# FPGA_POWER_AND_CONFIGURATION.net
KiCad netlist of a schematic drawn in Altium Designer
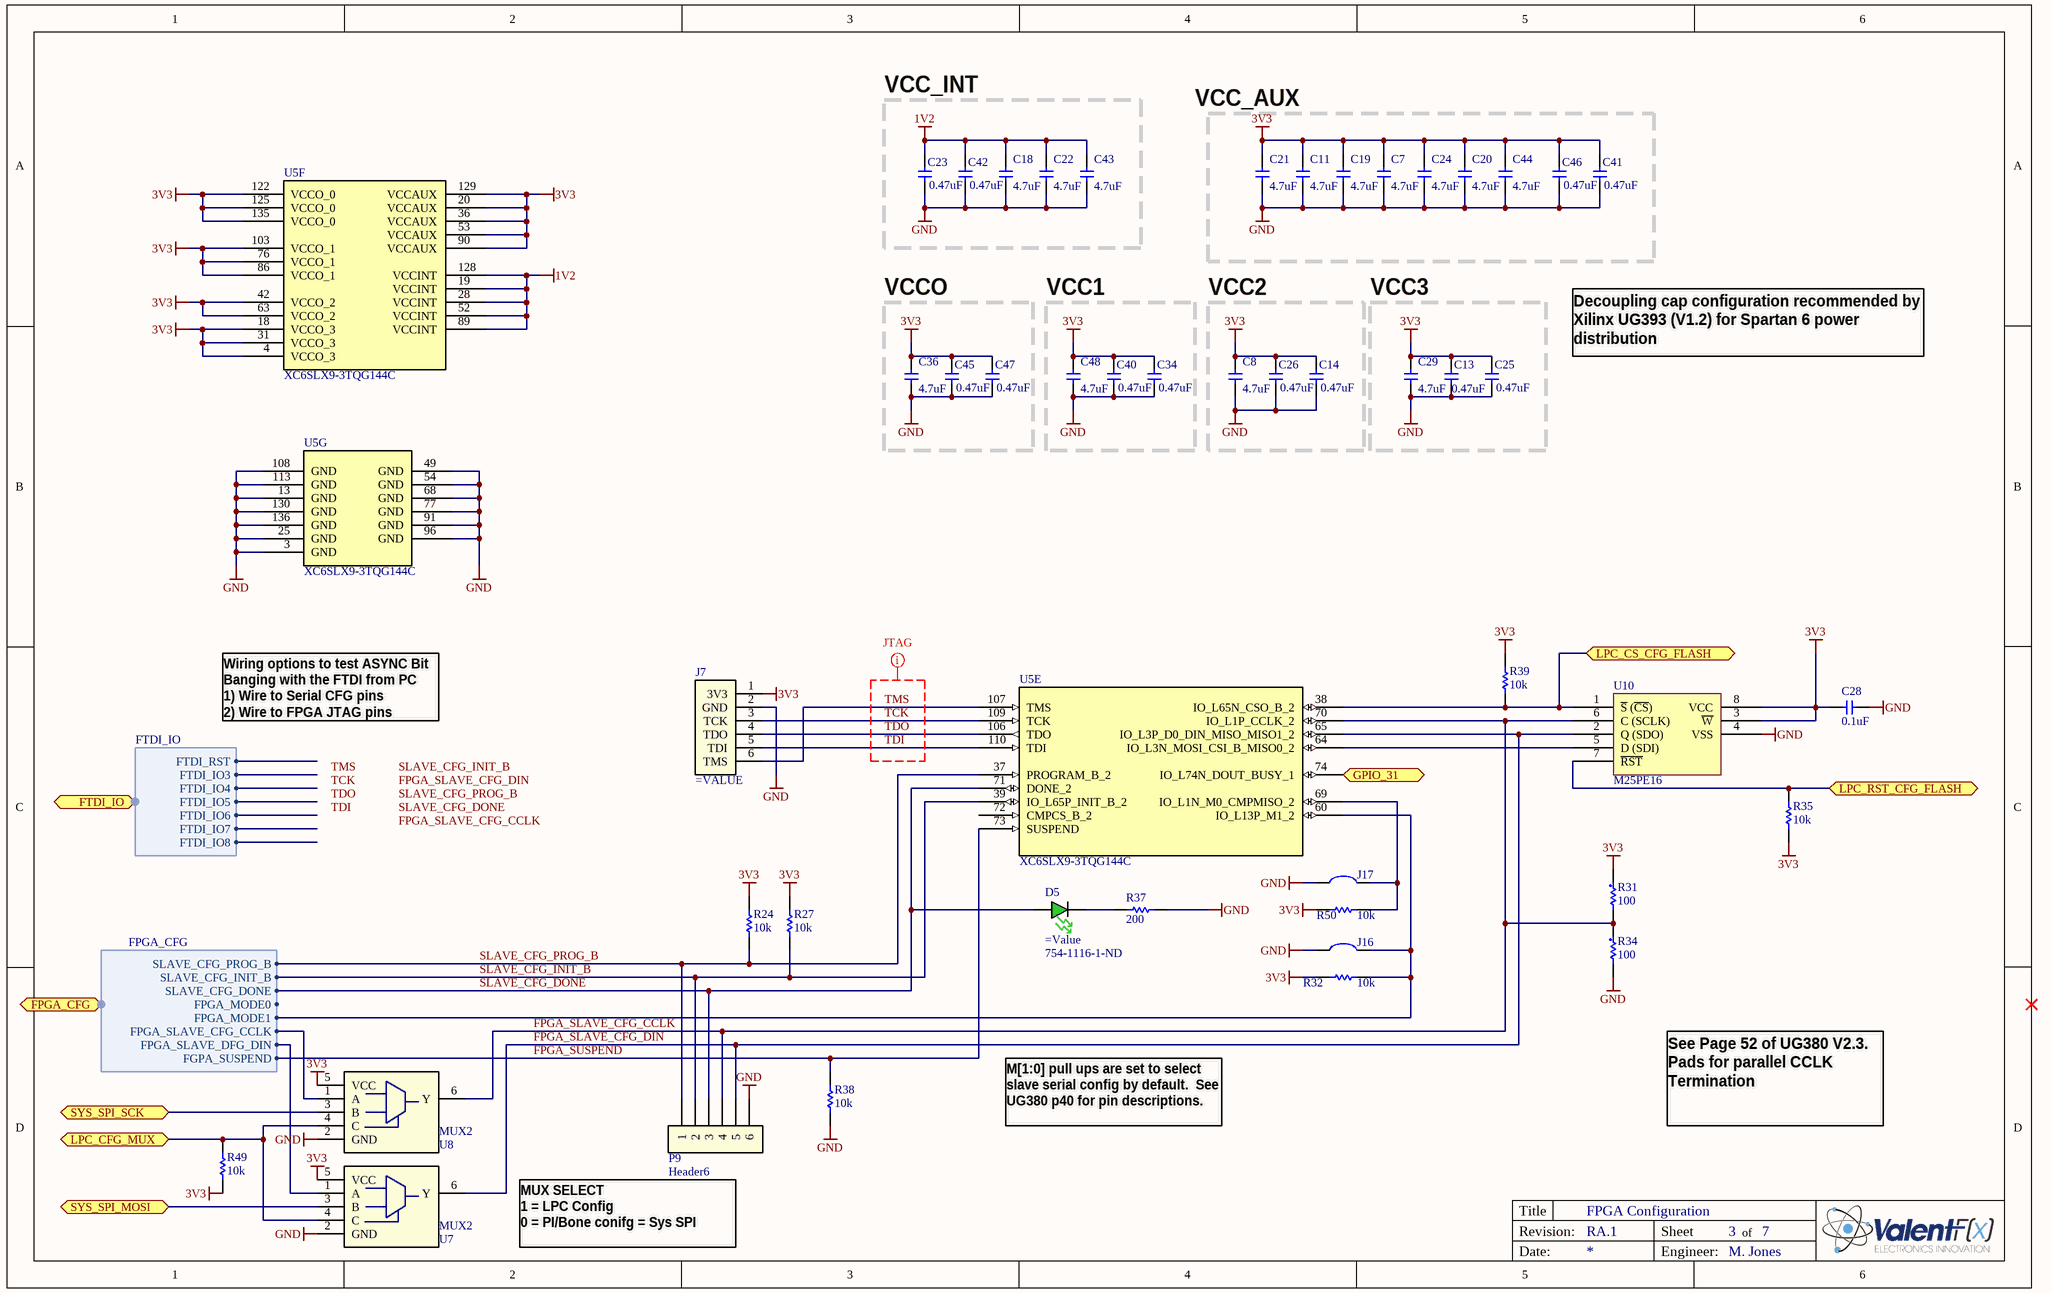
[diagram p0: FPGA_POWER_AND_CONFIGURATION.SchDoc]

(export (version "E")
  (design (tool "Eeschema 10.0.6"))
  (components
    (comp (ref "C7")
      (value "4.7uF")
      (footprint "C0603")
      (description "CAP CER 4.7UF 6.3V X5R 0603")
      (fields
        (field (name "MANUFACTURER") "Murata Electronics North America")
        (field (name "MANUFACTURER PART NUMBER") "GRM188R60J475KE19D")
      )
      (libsource (lib "eCapacitors") (part "GRM188R60J475KE19D"))
    )
    (comp (ref "C8")
      (value "4.7uF")
      (footprint "C0603")
      (description "CAP CER 4.7UF 6.3V X5R 0603")
      (fields
        (field (name "MANUFACTURER") "Murata Electronics North America")
        (field (name "MANUFACTURER PART NUMBER") "GRM188R60J475KE19D")
      )
      (libsource (lib "eCapacitors") (part "GRM188R60J475KE19D"))
    )
    (comp (ref "C11")
      (value "4.7uF")
      (footprint "C0603")
      (description "CAP CER 4.7UF 6.3V X5R 0603")
      (fields
        (field (name "MANUFACTURER") "Murata Electronics North America")
        (field (name "MANUFACTURER PART NUMBER") "GRM188R60J475KE19D")
      )
      (libsource (lib "eCapacitors") (part "GRM188R60J475KE19D"))
    )
    (comp (ref "C13")
      (value "0.47uF")
      (footprint "C0603")
      (description "CAP CER .47UF 25V X7R 0603")
      (fields
        (field (name "MANUFACTURER") "Murata Electronics North America")
        (field (name "MANUFACTURER PART NUMBER") "GCM188R71E474KA64D")
      )
      (libsource (lib "eCapacitors") (part "GCM188R71E474KA64D"))
    )
    (comp (ref "C14")
      (value "0.47uF")
      (footprint "C0603")
      (description "CAP CER .47UF 25V X7R 0603")
      (fields
        (field (name "MANUFACTURER") "Murata Electronics North America")
        (field (name "MANUFACTURER PART NUMBER") "GCM188R71E474KA64D")
      )
      (libsource (lib "eCapacitors") (part "GCM188R71E474KA64D"))
    )
    (comp (ref "C18")
      (value "4.7uF")
      (footprint "C0603")
      (description "CAP CER 4.7UF 6.3V X5R 0603")
      (fields
        (field (name "MANUFACTURER") "Murata Electronics North America")
        (field (name "MANUFACTURER PART NUMBER") "GRM188R60J475KE19D")
      )
      (libsource (lib "eCapacitors") (part "GRM188R60J475KE19D"))
    )
    (comp (ref "C19")
      (value "4.7uF")
      (footprint "C0603")
      (description "CAP CER 4.7UF 6.3V X5R 0603")
      (fields
        (field (name "MANUFACTURER") "Murata Electronics North America")
        (field (name "MANUFACTURER PART NUMBER") "GRM188R60J475KE19D")
      )
      (libsource (lib "eCapacitors") (part "GRM188R60J475KE19D"))
    )
    (comp (ref "C20")
      (value "4.7uF")
      (footprint "C0603")
      (description "CAP CER 4.7UF 6.3V X5R 0603")
      (fields
        (field (name "MANUFACTURER") "Murata Electronics North America")
        (field (name "MANUFACTURER PART NUMBER") "GRM188R60J475KE19D")
      )
      (libsource (lib "eCapacitors") (part "GRM188R60J475KE19D"))
    )
    (comp (ref "C21")
      (value "4.7uF")
      (footprint "C0603")
      (description "CAP CER 4.7UF 6.3V X5R 0603")
      (fields
        (field (name "MANUFACTURER") "Murata Electronics North America")
        (field (name "MANUFACTURER PART NUMBER") "GRM188R60J475KE19D")
      )
      (libsource (lib "eCapacitors") (part "GRM188R60J475KE19D"))
    )
    (comp (ref "C22")
      (value "4.7uF")
      (footprint "C0603")
      (description "CAP CER 4.7UF 6.3V X5R 0603")
      (fields
        (field (name "MANUFACTURER") "Murata Electronics North America")
        (field (name "MANUFACTURER PART NUMBER") "GRM188R60J475KE19D")
      )
      (libsource (lib "eCapacitors") (part "GRM188R60J475KE19D"))
    )
    (comp (ref "C23")
      (value "0.47uF")
      (footprint "C0603")
      (description "CAP CER .47UF 25V X7R 0603")
      (fields
        (field (name "MANUFACTURER") "Murata Electronics North America")
        (field (name "MANUFACTURER PART NUMBER") "GCM188R71E474KA64D")
      )
      (libsource (lib "eCapacitors") (part "GCM188R71E474KA64D"))
    )
    (comp (ref "C24")
      (value "4.7uF")
      (footprint "C0603")
      (description "CAP CER 4.7UF 6.3V X5R 0603")
      (fields
        (field (name "MANUFACTURER") "Murata Electronics North America")
        (field (name "MANUFACTURER PART NUMBER") "GRM188R60J475KE19D")
      )
      (libsource (lib "eCapacitors") (part "GRM188R60J475KE19D"))
    )
    (comp (ref "C25")
      (value "0.47uF")
      (footprint "C0603")
      (description "CAP CER .47UF 25V X7R 0603")
      (fields
        (field (name "MANUFACTURER") "Murata Electronics North America")
        (field (name "MANUFACTURER PART NUMBER") "GCM188R71E474KA64D")
      )
      (libsource (lib "eCapacitors") (part "GCM188R71E474KA64D"))
    )
    (comp (ref "C26")
      (value "0.47uF")
      (footprint "C0603")
      (description "CAP CER .47UF 25V X7R 0603")
      (fields
        (field (name "MANUFACTURER") "Murata Electronics North America")
        (field (name "MANUFACTURER PART NUMBER") "GCM188R71E474KA64D")
      )
      (libsource (lib "eCapacitors") (part "GCM188R71E474KA64D"))
    )
    (comp (ref "C28")
      (value "0.1uF")
      (footprint "C0603")
      (description "CAP CER .1UF 50V 10% X7R 0603")
      (fields
        (field (name "MANUFACTURER") "Murata Electronics North America")
        (field (name "MANUFACTURER PART NUMBER") "GRM188R71H104KA93D")
      )
      (libsource (lib "eCapacitors") (part "GRM188R71H104KA93D"))
    )
    (comp (ref "C29")
      (value "4.7uF")
      (footprint "C0603")
      (description "CAP CER 4.7UF 6.3V X5R 0603")
      (fields
        (field (name "MANUFACTURER") "Murata Electronics North America")
        (field (name "MANUFACTURER PART NUMBER") "GRM188R60J475KE19D")
      )
      (libsource (lib "eCapacitors") (part "GRM188R60J475KE19D"))
    )
    (comp (ref "C34")
      (value "0.47uF")
      (footprint "C0603")
      (description "CAP CER .47UF 25V X7R 0603")
      (fields
        (field (name "MANUFACTURER") "Murata Electronics North America")
        (field (name "MANUFACTURER PART NUMBER") "GCM188R71E474KA64D")
      )
      (libsource (lib "eCapacitors") (part "GCM188R71E474KA64D"))
    )
    (comp (ref "C36")
      (value "4.7uF")
      (footprint "C0603")
      (description "CAP CER 4.7UF 6.3V X5R 0603")
      (fields
        (field (name "MANUFACTURER") "Murata Electronics North America")
        (field (name "MANUFACTURER PART NUMBER") "GRM188R60J475KE19D")
      )
      (libsource (lib "eCapacitors") (part "GRM188R60J475KE19D"))
    )
    (comp (ref "C40")
      (value "0.47uF")
      (footprint "C0603")
      (description "CAP CER .47UF 25V X7R 0603")
      (fields
        (field (name "MANUFACTURER") "Murata Electronics North America")
        (field (name "MANUFACTURER PART NUMBER") "GCM188R71E474KA64D")
      )
      (libsource (lib "eCapacitors") (part "GCM188R71E474KA64D"))
    )
    (comp (ref "C41")
      (value "0.47uF")
      (footprint "C0603")
      (description "CAP CER .47UF 25V X7R 0603")
      (fields
        (field (name "MANUFACTURER") "Murata Electronics North America")
        (field (name "MANUFACTURER PART NUMBER") "GCM188R71E474KA64D")
      )
      (libsource (lib "eCapacitors") (part "GCM188R71E474KA64D"))
    )
    (comp (ref "C42")
      (value "0.47uF")
      (footprint "C0603")
      (description "CAP CER .47UF 25V X7R 0603")
      (fields
        (field (name "MANUFACTURER") "Murata Electronics North America")
        (field (name "MANUFACTURER PART NUMBER") "GCM188R71E474KA64D")
      )
      (libsource (lib "eCapacitors") (part "GCM188R71E474KA64D"))
    )
    (comp (ref "C43")
      (value "4.7uF")
      (footprint "C0603")
      (description "CAP CER 4.7UF 6.3V X5R 0603")
      (fields
        (field (name "MANUFACTURER") "Murata Electronics North America")
        (field (name "MANUFACTURER PART NUMBER") "GRM188R60J475KE19D")
      )
      (libsource (lib "eCapacitors") (part "GRM188R60J475KE19D"))
    )
    (comp (ref "C44")
      (value "4.7uF")
      (footprint "C0603")
      (description "CAP CER 4.7UF 6.3V X5R 0603")
      (fields
        (field (name "MANUFACTURER") "Murata Electronics North America")
        (field (name "MANUFACTURER PART NUMBER") "GRM188R60J475KE19D")
      )
      (libsource (lib "eCapacitors") (part "GRM188R60J475KE19D"))
    )
    (comp (ref "C45")
      (value "0.47uF")
      (footprint "C0603")
      (description "CAP CER .47UF 25V X7R 0603")
      (fields
        (field (name "MANUFACTURER") "Murata Electronics North America")
        (field (name "MANUFACTURER PART NUMBER") "GCM188R71E474KA64D")
      )
      (libsource (lib "eCapacitors") (part "GCM188R71E474KA64D"))
    )
    (comp (ref "C46")
      (value "0.47uF")
      (footprint "C0603")
      (description "CAP CER .47UF 25V X7R 0603")
      (fields
        (field (name "MANUFACTURER") "Murata Electronics North America")
        (field (name "MANUFACTURER PART NUMBER") "GCM188R71E474KA64D")
      )
      (libsource (lib "eCapacitors") (part "GCM188R71E474KA64D"))
    )
    (comp (ref "C47")
      (value "0.47uF")
      (footprint "C0603")
      (description "CAP CER .47UF 25V X7R 0603")
      (fields
        (field (name "MANUFACTURER") "Murata Electronics North America")
        (field (name "MANUFACTURER PART NUMBER") "GCM188R71E474KA64D")
      )
      (libsource (lib "eCapacitors") (part "GCM188R71E474KA64D"))
    )
    (comp (ref "C48")
      (value "4.7uF")
      (footprint "C0603")
      (description "CAP CER 4.7UF 6.3V X5R 0603")
      (fields
        (field (name "MANUFACTURER") "Murata Electronics North America")
        (field (name "MANUFACTURER PART NUMBER") "GRM188R60J475KE19D")
      )
      (libsource (lib "eCapacitors") (part "GRM188R60J475KE19D"))
    )
    (comp (ref "D5")
      (value "~")
      (footprint "LED_0603 - GREEN")
      (description "LED 1.6X0.8MM 570NM GRN CLR SMD")
      (fields
        (field (name "SUPPLIER PART NUMBER 1") "754-1116-1-ND")
        (field (name "MANUFACTURER") "Kingbright Corp")
        (field (name "MANUFACTURER PART NUMBER") "APT1608CGCK")
      )
      (libsource (lib "mDiode") (part "APT1608CGCK"))
    )
    (comp (ref "J7")
      (value "~")
      (footprint "JTAG - Digilent HS1")
      (description "DIGILENT - 410-205 - PROGRAMMING CABLE, JTAG HS1, USB2")
      (fields
        (field (name "MANUFACTURER") "Samtec")
        (field (name "MANUFACTURER PART NUMBER") "TSW-106-08-G-S-RA")
      )
      (libsource (lib "mConnector") (part "JTAG - Digilent HS1"))
    )
    (comp (ref "J16")
      (value "Solder Jumper")
      (footprint "SOLDER_JUMPER")
      (description "Solder/Configuration Jumper")
      (fields (field (name "MANUFACTURER") "n/a"))
      (libsource (lib "eConnector") (part "Solder Jumper"))
    )
    (comp (ref "J17")
      (value "Solder Jumper")
      (footprint "SOLDER_JUMPER")
      (description "Solder/Configuration Jumper")
      (fields (field (name "MANUFACTURER") "n/a"))
      (libsource (lib "eConnector") (part "Solder Jumper"))
    )
    (comp (ref "P9")
      (value "Header6")
      (footprint "HEADER_6_30_100 SMT SIP")
      (description "Header 6 pin")
      (libsource (lib "mConnector") (part "Header6"))
    )
    (comp (ref "R24")
      (value "10k")
      (footprint "R0603")
      (description "RES 10.0K OHM 1/10W 1% 0603 SMD")
      (fields
        (field (name "MANUFACTURER") "Panasonic - ECG")
        (field (name "MANUFACTURER PART NUMBER") "ERJ-3EKF1002V")
      )
      (libsource (lib "eResistors") (part "ERJ-3EKF1002V"))
    )
    (comp (ref "R27")
      (value "10k")
      (footprint "R0603")
      (description "RES 10.0K OHM 1/10W 1% 0603 SMD")
      (fields
        (field (name "MANUFACTURER") "Panasonic - ECG")
        (field (name "MANUFACTURER PART NUMBER") "ERJ-3EKF1002V")
      )
      (libsource (lib "eResistors") (part "ERJ-3EKF1002V"))
    )
    (comp (ref "R31")
      (value "100")
      (footprint "mRCL:R0603")
      (description "100 ohms 1% Thick Film Resistors - SMD 1/10watt")
      (fields
        (field (name "MANUFACTURER") "Vishay/Dale")
        (field (name "MANUFACTURER PART NUMBER") "CRCW0603100RFKEA")
      )
      (libsource (lib "mResistors") (part "R0603 - CRCW0603100RFKEA"))
    )
    (comp (ref "R32")
      (value "10k")
      (footprint "R0603")
      (description "RES 10.0K OHM 1/10W 1% 0603 SMD")
      (fields
        (field (name "MANUFACTURER") "Panasonic - ECG")
        (field (name "MANUFACTURER PART NUMBER") "ERJ-3EKF1002V")
      )
      (libsource (lib "eResistors") (part "ERJ-3EKF1002V"))
    )
    (comp (ref "R34")
      (value "100")
      (footprint "mRCL:R0603")
      (description "100 ohms 1% Thick Film Resistors - SMD 1/10watt")
      (fields
        (field (name "MANUFACTURER") "Vishay/Dale")
        (field (name "MANUFACTURER PART NUMBER") "CRCW0603100RFKEA")
      )
      (libsource (lib "mResistors") (part "R0603 - CRCW0603100RFKEA"))
    )
    (comp (ref "R35")
      (value "10k")
      (footprint "R0603")
      (description "RES 10.0K OHM 1/10W 1% 0603 SMD")
      (fields
        (field (name "MANUFACTURER") "Panasonic - ECG")
        (field (name "MANUFACTURER PART NUMBER") "ERJ-3EKF1002V")
      )
      (libsource (lib "eResistors") (part "ERJ-3EKF1002V"))
    )
    (comp (ref "R37")
      (value "200")
      (footprint "R0603")
      (description "RES 200 OHM 1/10W 1% 0603 SMD")
      (fields
        (field (name "MANUFACTURER") "Panasonic - ECG")
        (field (name "MANUFACTURER PART NUMBER") "ERJ-3EKF2000V")
      )
      (libsource (lib "eResistors") (part "ERJ-3EKF2000V"))
    )
    (comp (ref "R38")
      (value "10k")
      (footprint "R0603")
      (description "RES 10.0K OHM 1/10W 1% 0603 SMD")
      (fields
        (field (name "MANUFACTURER") "Panasonic - ECG")
        (field (name "MANUFACTURER PART NUMBER") "ERJ-3EKF1002V")
      )
      (libsource (lib "eResistors") (part "ERJ-3EKF1002V"))
    )
    (comp (ref "R39")
      (value "10k")
      (footprint "R0603")
      (description "RES 10.0K OHM 1/10W 1% 0603 SMD")
      (fields
        (field (name "MANUFACTURER") "Panasonic - ECG")
        (field (name "MANUFACTURER PART NUMBER") "ERJ-3EKF1002V")
      )
      (libsource (lib "eResistors") (part "ERJ-3EKF1002V"))
    )
    (comp (ref "R49")
      (value "10k")
      (footprint "R0603")
      (description "RES 10.0K OHM 1/10W 1% 0603 SMD")
      (fields
        (field (name "MANUFACTURER") "Panasonic - ECG")
        (field (name "MANUFACTURER PART NUMBER") "ERJ-3EKF1002V")
      )
      (libsource (lib "eResistors") (part "ERJ-3EKF1002V"))
    )
    (comp (ref "R50")
      (value "10k")
      (footprint "R0603")
      (description "RES 10.0K OHM 1/10W 1% 0603 SMD")
      (fields
        (field (name "MANUFACTURER") "Panasonic - ECG")
        (field (name "MANUFACTURER PART NUMBER") "ERJ-3EKF1002V")
      )
      (libsource (lib "eResistors") (part "ERJ-3EKF1002V"))
    )
    (comp (ref "U5")
      (value "XC6SLX9-3TQG144C")
      (footprint "TQ144_L")
      (description "IC FPAG SPARTAN 6 9K 144TQFP")
      (fields (field (name "MANUFACTURER") "Xilinx Inc"))
      (libsource (lib "eIC") (part "XC6SLX9-3TQG144C"))
    )
    (comp (ref "U7")
      (value "MUX2")
      (footprint "SC70-6")
      (description "IC BUFF/MUX SCHMITT-TRIG SC70-6")
      (fields
        (field (name "MANUFACTURER") "Texas Instruments")
        (field (name "MANUFACTURER PART NUMBER") "SN74AUP1T157DCKR")
      )
      (libsource (lib "mIC") (part "MUX - SN74AUP1T157DCKR"))
    )
    (comp (ref "U8")
      (value "MUX2")
      (footprint "SC70-6")
      (description "IC BUFF/MUX SCHMITT-TRIG SC70-6")
      (fields
        (field (name "MANUFACTURER") "Texas Instruments")
        (field (name "MANUFACTURER PART NUMBER") "SN74AUP1T157DCKR")
      )
      (libsource (lib "mIC") (part "MUX - SN74AUP1T157DCKR"))
    )
    (comp (ref "U10")
      (value "M25PE16")
      (footprint "SOIC127P830X200-8L")
      (description "IC FLASH 16MBIT 75MHZ 8SOIC")
      (fields
        (field (name "MANUFACTURER") "Numonyx/ST Micro")
        (field (name "MANUFACTURER PART NUMBER") "M25PE16-VMW6TG")
      )
      (libsource (lib "ICs") (part "M25PE16-VMW6TG"))
    )
  )
  (nets
    (net (code "3") (name "/FPGA_MODE1") (class "Default")
      (node (ref "J16") (pin "1") (pinfunction "1_1") (pintype "passive"))
      (node (ref "R32") (pin "2") (pinfunction "2_2") (pintype "passive"))
      (node (ref "U5") (pin "60") (pinfunction "IO_L13P_M1_2_60") (pintype "bidirectional"))
    )
    (net (code "4") (name "/FPGA_SLAVE_CFG_CCLK") (class "Default")
      (node (ref "P9") (pin "4") (pinfunction "4_4") (pintype "passive"))
      (node (ref "R31") (pin "2") (pinfunction "2_2") (pintype "passive"))
      (node (ref "R34") (pin "1") (pinfunction "1_1") (pintype "passive"))
      (node (ref "U10") (pin "6") (pinfunction "C_(SCLK)_6") (pintype "passive"))
      (node (ref "U5") (pin "70") (pinfunction "IO_L1P_CCLK_2_70") (pintype "bidirectional"))
      (node (ref "U8") (pin "6") (pinfunction "Y_6") (pintype "passive"))
    )
    (net (code "5") (name "/FPGA_SLAVE_CFG_DIN") (class "Default")
      (node (ref "P9") (pin "5") (pinfunction "5_5") (pintype "passive"))
      (node (ref "U10") (pin "2") (pinfunction "Q_(SDO)_2") (pintype "passive"))
      (node (ref "U5") (pin "65") (pinfunction "IO_L3P_D0_DIN_MISO_MISO1_2_65") (pintype "bidirectional"))
      (node (ref "U7") (pin "6") (pinfunction "Y_6") (pintype "passive"))
    )
    (net (code "6") (name "/FPGA_SLAVE_DFG_DIN") (class "Default")
      (node (ref "U7") (pin "1") (pinfunction "A_1") (pintype "passive"))
    )
    (net (code "7") (name "/FPGA_SUSPEND") (class "Default")
      (node (ref "R38") (pin "2") (pinfunction "2_2") (pintype "passive"))
      (node (ref "U5") (pin "73") (pinfunction "SUSPEND_73") (pintype "input"))
    )
    (net (code "15") (name "/GPIO_31") (class "Default")
      (node (ref "U5") (pin "74") (pinfunction "IO_L74N_DOUT_BUSY_1_74") (pintype "bidirectional"))
    )
    (net (code "16") (name "/LPC_CFG_MUX") (class "Default")
      (node (ref "R49") (pin "2") (pinfunction "2_2") (pintype "passive"))
      (node (ref "U7") (pin "4") (pinfunction "C_4") (pintype "passive"))
      (node (ref "U8") (pin "4") (pinfunction "C_4") (pintype "passive"))
    )
    (net (code "17") (name "/LPC_CS_CFG_FLASH") (class "Default")
      (node (ref "R39") (pin "1") (pinfunction "1_1") (pintype "passive"))
      (node (ref "U10") (pin "1") (pinfunction "~{S}_(~{CS})_1") (pintype "passive"))
      (node (ref "U5") (pin "38") (pinfunction "IO_L65N_CSO_B_2_38") (pintype "bidirectional"))
    )
    (net (code "18") (name "/LPC_RST_CFG_FLASH") (class "Default")
      (node (ref "R35") (pin "1") (pinfunction "1_1") (pintype "passive"))
      (node (ref "U10") (pin "7") (pinfunction "~{RST}_7") (pintype "passive"))
    )
    (net (code "19") (name "/SLAVE_CFG_DONE") (class "Default")
      (node (ref "D5") (pin "A") (pinfunction "A_A") (pintype "passive"))
      (node (ref "P9") (pin "3") (pinfunction "3_3") (pintype "passive"))
      (node (ref "U5") (pin "71") (pinfunction "DONE_2_71") (pintype "bidirectional"))
    )
    (net (code "20") (name "/SLAVE_CFG_INIT_B") (class "Default")
      (node (ref "P9") (pin "2") (pinfunction "2_2") (pintype "passive"))
      (node (ref "R27") (pin "1") (pinfunction "1_1") (pintype "passive"))
      (node (ref "U5") (pin "39") (pinfunction "IO_L65P_INIT_B_2_39") (pintype "bidirectional"))
    )
    (net (code "21") (name "/SLAVE_CFG_PROG_B") (class "Default")
      (node (ref "P9") (pin "1") (pinfunction "1_1") (pintype "passive"))
      (node (ref "R24") (pin "1") (pinfunction "1_1") (pintype "passive"))
      (node (ref "U5") (pin "37") (pinfunction "PROGRAM_B_2_37") (pintype "input"))
    )
    (net (code "22") (name "/SYS_SPI_MOSI") (class "Default")
      (node (ref "U7") (pin "3") (pinfunction "B_3") (pintype "passive"))
    )
    (net (code "23") (name "/SYS_SPI_SCK") (class "Default")
      (node (ref "U8") (pin "3") (pinfunction "B_3") (pintype "passive"))
    )
    (net (code "24") (name "/TCK") (class "Default")
      (node (ref "J7") (pin "3") (pinfunction "TCK_3") (pintype "passive"))
      (node (ref "U5") (pin "109") (pinfunction "TCK_109") (pintype "input"))
    )
    (net (code "25") (name "/TDI") (class "Default")
      (node (ref "J7") (pin "5") (pinfunction "TDI_5") (pintype "passive"))
      (node (ref "U5") (pin "110") (pinfunction "TDI_110") (pintype "input"))
    )
    (net (code "26") (name "/TDO") (class "Default")
      (node (ref "J7") (pin "4") (pinfunction "TDO_4") (pintype "passive"))
      (node (ref "U5") (pin "106") (pinfunction "TDO_106") (pintype "output"))
    )
    (net (code "27") (name "/TMS") (class "Default")
      (node (ref "J7") (pin "6") (pinfunction "TMS_6") (pintype "passive"))
      (node (ref "U5") (pin "107") (pinfunction "TMS_107") (pintype "input"))
    )
    (net (code "30") (name "1V2") (class "Default")
      (node (ref "C18") (pin "2") (pinfunction "2_2") (pintype "passive"))
      (node (ref "C22") (pin "2") (pinfunction "2_2") (pintype "passive"))
      (node (ref "C23") (pin "2") (pinfunction "2_2") (pintype "passive"))
      (node (ref "C42") (pin "2") (pinfunction "2_2") (pintype "passive"))
      (node (ref "C43") (pin "2") (pinfunction "2_2") (pintype "passive"))
      (node (ref "U5") (pin "128") (pinfunction "VCCINT_128") (pintype "power_in"))
      (node (ref "U5") (pin "19") (pinfunction "VCCINT_19") (pintype "power_in"))
      (node (ref "U5") (pin "28") (pinfunction "VCCINT_28") (pintype "power_in"))
      (node (ref "U5") (pin "52") (pinfunction "VCCINT_52") (pintype "power_in"))
      (node (ref "U5") (pin "89") (pinfunction "VCCINT_89") (pintype "power_in"))
    )
    (net (code "31") (name "3V3") (class "Default")
      (node (ref "C11") (pin "2") (pinfunction "2_2") (pintype "passive"))
      (node (ref "C13") (pin "2") (pinfunction "2_2") (pintype "passive"))
      (node (ref "C14") (pin "2") (pinfunction "2_2") (pintype "passive"))
      (node (ref "C19") (pin "2") (pinfunction "2_2") (pintype "passive"))
      (node (ref "C20") (pin "2") (pinfunction "2_2") (pintype "passive"))
      (node (ref "C21") (pin "2") (pinfunction "2_2") (pintype "passive"))
      (node (ref "C24") (pin "2") (pinfunction "2_2") (pintype "passive"))
      (node (ref "C25") (pin "2") (pinfunction "2_2") (pintype "passive"))
      (node (ref "C26") (pin "2") (pinfunction "2_2") (pintype "passive"))
      (node (ref "C28") (pin "1") (pinfunction "1_1") (pintype "passive"))
      (node (ref "C29") (pin "2") (pinfunction "2_2") (pintype "passive"))
      (node (ref "C34") (pin "2") (pinfunction "2_2") (pintype "passive"))
      (node (ref "C36") (pin "2") (pinfunction "2_2") (pintype "passive"))
      (node (ref "C40") (pin "2") (pinfunction "2_2") (pintype "passive"))
      (node (ref "C41") (pin "2") (pinfunction "2_2") (pintype "passive"))
      (node (ref "C44") (pin "2") (pinfunction "2_2") (pintype "passive"))
      (node (ref "C45") (pin "2") (pinfunction "2_2") (pintype "passive"))
      (node (ref "C46") (pin "2") (pinfunction "2_2") (pintype "passive"))
      (node (ref "C47") (pin "2") (pinfunction "2_2") (pintype "passive"))
      (node (ref "C48") (pin "2") (pinfunction "2_2") (pintype "passive"))
      (node (ref "C7") (pin "2") (pinfunction "2_2") (pintype "passive"))
      (node (ref "C8") (pin "2") (pinfunction "2_2") (pintype "passive"))
      (node (ref "J7") (pin "1") (pinfunction "3V3_1") (pintype "passive"))
      (node (ref "R24") (pin "2") (pinfunction "2_2") (pintype "passive"))
      (node (ref "R27") (pin "2") (pinfunction "2_2") (pintype "passive"))
      (node (ref "R31") (pin "1") (pinfunction "1_1") (pintype "passive"))
      (node (ref "R32") (pin "1") (pinfunction "1_1") (pintype "passive"))
      (node (ref "R35") (pin "2") (pinfunction "2_2") (pintype "passive"))
      (node (ref "R39") (pin "2") (pinfunction "2_2") (pintype "passive"))
      (node (ref "R49") (pin "1") (pinfunction "1_1") (pintype "passive"))
      (node (ref "R50") (pin "1") (pinfunction "1_1") (pintype "passive"))
      (node (ref "U10") (pin "3") (pinfunction "~{W}_3") (pintype "passive"))
      (node (ref "U10") (pin "8") (pinfunction "VCC_8") (pintype "passive"))
      (node (ref "U5") (pin "103") (pinfunction "VCCO_1_103") (pintype "power_in"))
      (node (ref "U5") (pin "122") (pinfunction "VCCO_0_122") (pintype "power_in"))
      (node (ref "U5") (pin "125") (pinfunction "VCCO_0_125") (pintype "power_in"))
      (node (ref "U5") (pin "129") (pinfunction "VCCAUX_129") (pintype "power_in"))
      (node (ref "U5") (pin "135") (pinfunction "VCCO_0_135") (pintype "power_in"))
      (node (ref "U5") (pin "18") (pinfunction "VCCO_3_18") (pintype "power_in"))
      (node (ref "U5") (pin "20") (pinfunction "VCCAUX_20") (pintype "power_in"))
      (node (ref "U5") (pin "31") (pinfunction "VCCO_3_31") (pintype "power_in"))
      (node (ref "U5") (pin "36") (pinfunction "VCCAUX_36") (pintype "power_in"))
      (node (ref "U5") (pin "4") (pinfunction "VCCO_3_4") (pintype "power_in"))
      (node (ref "U5") (pin "42") (pinfunction "VCCO_2_42") (pintype "power_in"))
      (node (ref "U5") (pin "53") (pinfunction "VCCAUX_53") (pintype "power_in"))
      (node (ref "U5") (pin "63") (pinfunction "VCCO_2_63") (pintype "power_in"))
      (node (ref "U5") (pin "76") (pinfunction "VCCO_1_76") (pintype "power_in"))
      (node (ref "U5") (pin "86") (pinfunction "VCCO_1_86") (pintype "power_in"))
      (node (ref "U5") (pin "90") (pinfunction "VCCAUX_90") (pintype "power_in"))
      (node (ref "U7") (pin "5") (pinfunction "VCC_5") (pintype "passive"))
      (node (ref "U8") (pin "5") (pinfunction "VCC_5") (pintype "passive"))
    )
    (net (code "32") (name "GND") (class "Default")
      (node (ref "C11") (pin "1") (pinfunction "1_1") (pintype "passive"))
      (node (ref "C13") (pin "1") (pinfunction "1_1") (pintype "passive"))
      (node (ref "C14") (pin "1") (pinfunction "1_1") (pintype "passive"))
      (node (ref "C18") (pin "1") (pinfunction "1_1") (pintype "passive"))
      (node (ref "C19") (pin "1") (pinfunction "1_1") (pintype "passive"))
      (node (ref "C20") (pin "1") (pinfunction "1_1") (pintype "passive"))
      (node (ref "C21") (pin "1") (pinfunction "1_1") (pintype "passive"))
      (node (ref "C22") (pin "1") (pinfunction "1_1") (pintype "passive"))
      (node (ref "C23") (pin "1") (pinfunction "1_1") (pintype "passive"))
      (node (ref "C24") (pin "1") (pinfunction "1_1") (pintype "passive"))
      (node (ref "C25") (pin "1") (pinfunction "1_1") (pintype "passive"))
      (node (ref "C26") (pin "1") (pinfunction "1_1") (pintype "passive"))
      (node (ref "C28") (pin "2") (pinfunction "2_2") (pintype "passive"))
      (node (ref "C29") (pin "1") (pinfunction "1_1") (pintype "passive"))
      (node (ref "C34") (pin "1") (pinfunction "1_1") (pintype "passive"))
      (node (ref "C36") (pin "1") (pinfunction "1_1") (pintype "passive"))
      (node (ref "C40") (pin "1") (pinfunction "1_1") (pintype "passive"))
      (node (ref "C41") (pin "1") (pinfunction "1_1") (pintype "passive"))
      (node (ref "C42") (pin "1") (pinfunction "1_1") (pintype "passive"))
      (node (ref "C43") (pin "1") (pinfunction "1_1") (pintype "passive"))
      (node (ref "C44") (pin "1") (pinfunction "1_1") (pintype "passive"))
      (node (ref "C45") (pin "1") (pinfunction "1_1") (pintype "passive"))
      (node (ref "C46") (pin "1") (pinfunction "1_1") (pintype "passive"))
      (node (ref "C47") (pin "1") (pinfunction "1_1") (pintype "passive"))
      (node (ref "C48") (pin "1") (pinfunction "1_1") (pintype "passive"))
      (node (ref "C7") (pin "1") (pinfunction "1_1") (pintype "passive"))
      (node (ref "C8") (pin "1") (pinfunction "1_1") (pintype "passive"))
      (node (ref "J16") (pin "2") (pinfunction "2_2") (pintype "passive"))
      (node (ref "J17") (pin "2") (pinfunction "2_2") (pintype "passive"))
      (node (ref "J7") (pin "2") (pinfunction "GND_2") (pintype "passive"))
      (node (ref "P9") (pin "6") (pinfunction "6_6") (pintype "passive"))
      (node (ref "R34") (pin "2") (pinfunction "2_2") (pintype "passive"))
      (node (ref "R37") (pin "2") (pinfunction "2_2") (pintype "passive"))
      (node (ref "R38") (pin "1") (pinfunction "1_1") (pintype "passive"))
      (node (ref "U10") (pin "4") (pinfunction "VSS_4") (pintype "passive"))
      (node (ref "U5") (pin "108") (pinfunction "GND_108") (pintype "power_in"))
      (node (ref "U5") (pin "113") (pinfunction "GND_113") (pintype "power_in"))
      (node (ref "U5") (pin "13") (pinfunction "GND_13") (pintype "power_in"))
      (node (ref "U5") (pin "130") (pinfunction "GND_130") (pintype "power_in"))
      (node (ref "U5") (pin "136") (pinfunction "GND_136") (pintype "power_in"))
      (node (ref "U5") (pin "25") (pinfunction "GND_25") (pintype "power_in"))
      (node (ref "U5") (pin "3") (pinfunction "GND_3") (pintype "power_in"))
      (node (ref "U5") (pin "49") (pinfunction "GND_49") (pintype "power_in"))
      (node (ref "U5") (pin "54") (pinfunction "GND_54") (pintype "power_in"))
      (node (ref "U5") (pin "68") (pinfunction "GND_68") (pintype "power_in"))
      (node (ref "U5") (pin "77") (pinfunction "GND_77") (pintype "power_in"))
      (node (ref "U5") (pin "91") (pinfunction "GND_91") (pintype "power_in"))
      (node (ref "U5") (pin "96") (pinfunction "GND_96") (pintype "power_in"))
      (node (ref "U7") (pin "2") (pinfunction "GND_2") (pintype "passive"))
      (node (ref "U8") (pin "2") (pinfunction "GND_2") (pintype "passive"))
    )
    (net (code "33") (name "Net-(D5-PadC)") (class "Default")
      (node (ref "D5") (pin "C") (pinfunction "C_C") (pintype "passive"))
      (node (ref "R37") (pin "1") (pinfunction "1_1") (pintype "passive"))
    )
    (net (code "34") (name "Net-(U5E-IO_L1N_M0_CMPMISO_2)") (class "Default")
      (node (ref "J17") (pin "1") (pinfunction "1_1") (pintype "passive"))
      (node (ref "R50") (pin "2") (pinfunction "2_2") (pintype "passive"))
      (node (ref "U5") (pin "69") (pinfunction "IO_L1N_M0_CMPMISO_2_69") (pintype "bidirectional"))
    )
    (net (code "35") (name "Net-(U10-D_(SDI))") (class "Default")
      (node (ref "U10") (pin "5") (pinfunction "D_(SDI)_5") (pintype "passive"))
      (node (ref "U5") (pin "64") (pinfunction "IO_L3N_MOSI_CSI_B_MISO0_2_64") (pintype "bidirectional"))
    )
    (net (code "36") (name "unconnected-(U5E-CMPCS_B_2-Pad72)") (class "Default")
      (node (ref "U5") (pin "72") (pinfunction "CMPCS_B_2_72") (pintype "input"))
    )
    (net (code "37") (name "unconnected-(U8-A-Pad1)") (class "Default")
      (node (ref "U8") (pin "1") (pinfunction "A_1") (pintype "passive"))
    )
  )
)
